# Bank33.net
KiCad netlist of a schematic drawn in Altium Designer
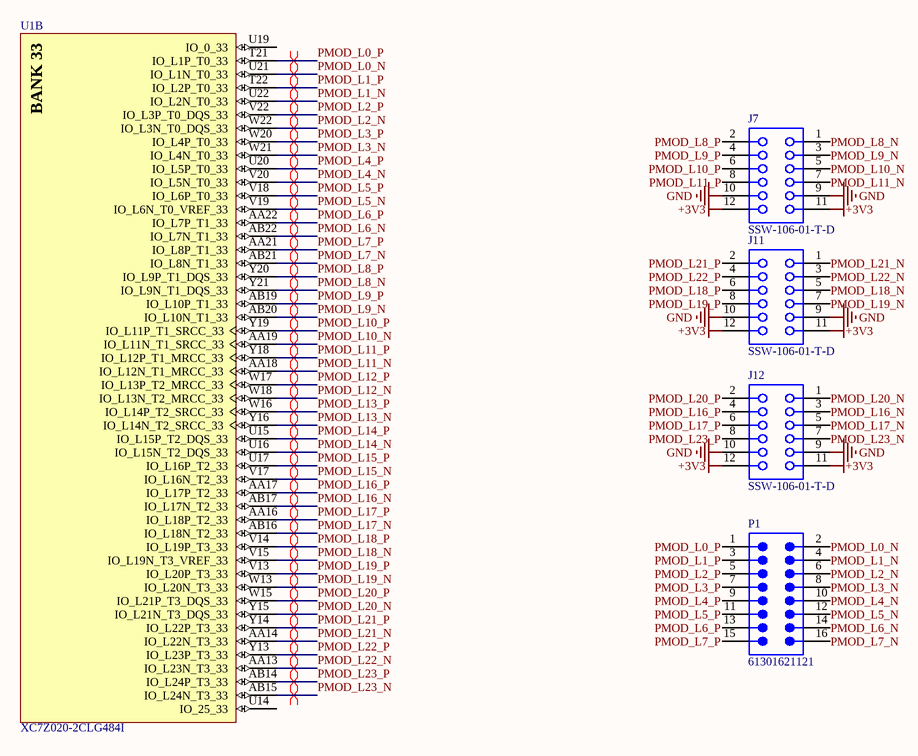
[diagram p0: Bank33.SchDoc]

(export (version "E")
  (design (tool "Eeschema 10.0.6"))
  (components
    (comp (ref "J7")
      (value "SSW-106-01-T-D")
      (footprint "SMTC-SSW-106-01-X-D")
      (description "SQ Post Socket, Through-hole, Vertical, -55 to 105 degC, 2.54mm Pitch, 12-Pin, Female, RoHS")
      (fields (field (name "MANUFACTURER") "Samtec"))
      (libsource (lib "Altium Content Vault") (part "SMTC-SSW-106-01-X-D"))
    )
    (comp (ref "J11")
      (value "SSW-106-01-T-D")
      (footprint "SMTC-SSW-106-01-X-D")
      (description "SQ Post Socket, Through-hole, Vertical, -55 to 105 degC, 2.54mm Pitch, 12-Pin, Female, RoHS")
      (fields (field (name "MANUFACTURER") "Samtec"))
      (libsource (lib "Altium Content Vault") (part "SMTC-SSW-106-01-X-D"))
    )
    (comp (ref "J12")
      (value "SSW-106-01-T-D")
      (footprint "SMTC-SSW-106-01-X-D")
      (description "SQ Post Socket, Through-hole, Vertical, -55 to 105 degC, 2.54mm Pitch, 12-Pin, Female, RoHS")
      (fields (field (name "MANUFACTURER") "Samtec"))
      (libsource (lib "Altium Content Vault") (part "SMTC-SSW-106-01-X-D"))
    )
    (comp (ref "P1")
      (value "61301621121")
      (footprint "61301621121")
      (libsource (lib "Altium Content Vault") (part "Header_Male_2R_16P"))
    )
    (comp (ref "U1")
      (value "XC7Z020-2CLG484I")
      (footprint "CLG484")
      (fields (field (name "GENERIC PART NUMBER") "XC7Z020"))
      (libsource (lib "Altium Content Vault") (part "XNLX-XC7Z020-CLG484"))
    )
  )
  (nets
    (net (code "1") (name "+3V3") (class "Default")
      (node (ref "J11") (pin "11") (pinfunction "11_11") (pintype "passive"))
      (node (ref "J11") (pin "12") (pinfunction "12_12") (pintype "passive"))
      (node (ref "J12") (pin "11") (pinfunction "11_11") (pintype "passive"))
      (node (ref "J12") (pin "12") (pinfunction "12_12") (pintype "passive"))
      (node (ref "J7") (pin "11") (pinfunction "11_11") (pintype "passive"))
      (node (ref "J7") (pin "12") (pinfunction "12_12") (pintype "passive"))
    )
    (net (code "2") (name "/PMOD_L0_N") (class "Default")
      (node (ref "P1") (pin "2") (pinfunction "2_2") (pintype "passive"))
      (node (ref "U1") (pin "U21") (pinfunction "IO_L1N_T0_33_U21") (pintype "bidirectional"))
    )
    (net (code "3") (name "/PMOD_L0_P") (class "Default")
      (node (ref "P1") (pin "1") (pinfunction "1_1") (pintype "passive"))
      (node (ref "U1") (pin "T21") (pinfunction "IO_L1P_T0_33_T21") (pintype "bidirectional"))
    )
    (net (code "4") (name "/PMOD_L1_N") (class "Default")
      (node (ref "P1") (pin "4") (pinfunction "4_4") (pintype "passive"))
      (node (ref "U1") (pin "U22") (pinfunction "IO_L2N_T0_33_U22") (pintype "bidirectional"))
    )
    (net (code "5") (name "/PMOD_L1_P") (class "Default")
      (node (ref "P1") (pin "3") (pinfunction "3_3") (pintype "passive"))
      (node (ref "U1") (pin "T22") (pinfunction "IO_L2P_T0_33_T22") (pintype "bidirectional"))
    )
    (net (code "6") (name "/PMOD_L2_N") (class "Default")
      (node (ref "P1") (pin "6") (pinfunction "6_6") (pintype "passive"))
      (node (ref "U1") (pin "W22") (pinfunction "IO_L3N_T0_DQS_33_W22") (pintype "bidirectional"))
    )
    (net (code "7") (name "/PMOD_L2_P") (class "Default")
      (node (ref "P1") (pin "5") (pinfunction "5_5") (pintype "passive"))
      (node (ref "U1") (pin "V22") (pinfunction "IO_L3P_T0_DQS_33_V22") (pintype "bidirectional"))
    )
    (net (code "8") (name "/PMOD_L3_N") (class "Default")
      (node (ref "P1") (pin "8") (pinfunction "8_8") (pintype "passive"))
      (node (ref "U1") (pin "W21") (pinfunction "IO_L4N_T0_33_W21") (pintype "bidirectional"))
    )
    (net (code "9") (name "/PMOD_L3_P") (class "Default")
      (node (ref "P1") (pin "7") (pinfunction "7_7") (pintype "passive"))
      (node (ref "U1") (pin "W20") (pinfunction "IO_L4P_T0_33_W20") (pintype "bidirectional"))
    )
    (net (code "10") (name "/PMOD_L4_N") (class "Default")
      (node (ref "P1") (pin "10") (pinfunction "10_10") (pintype "passive"))
      (node (ref "U1") (pin "V20") (pinfunction "IO_L5N_T0_33_V20") (pintype "bidirectional"))
    )
    (net (code "11") (name "/PMOD_L4_P") (class "Default")
      (node (ref "P1") (pin "9") (pinfunction "9_9") (pintype "passive"))
      (node (ref "U1") (pin "U20") (pinfunction "IO_L5P_T0_33_U20") (pintype "bidirectional"))
    )
    (net (code "12") (name "/PMOD_L5_N") (class "Default")
      (node (ref "P1") (pin "12") (pinfunction "12_12") (pintype "passive"))
      (node (ref "U1") (pin "V19") (pinfunction "IO_L6N_T0_VREF_33_V19") (pintype "bidirectional"))
    )
    (net (code "13") (name "/PMOD_L5_P") (class "Default")
      (node (ref "P1") (pin "11") (pinfunction "11_11") (pintype "passive"))
      (node (ref "U1") (pin "V18") (pinfunction "IO_L6P_T0_33_V18") (pintype "bidirectional"))
    )
    (net (code "14") (name "/PMOD_L6_N") (class "Default")
      (node (ref "P1") (pin "14") (pinfunction "14_14") (pintype "passive"))
      (node (ref "U1") (pin "AB22") (pinfunction "IO_L7N_T1_33_AB22") (pintype "bidirectional"))
    )
    (net (code "15") (name "/PMOD_L6_P") (class "Default")
      (node (ref "P1") (pin "13") (pinfunction "13_13") (pintype "passive"))
      (node (ref "U1") (pin "AA22") (pinfunction "IO_L7P_T1_33_AA22") (pintype "bidirectional"))
    )
    (net (code "16") (name "/PMOD_L7_N") (class "Default")
      (node (ref "P1") (pin "16") (pinfunction "16_16") (pintype "passive"))
      (node (ref "U1") (pin "AB21") (pinfunction "IO_L8N_T1_33_AB21") (pintype "bidirectional"))
    )
    (net (code "17") (name "/PMOD_L7_P") (class "Default")
      (node (ref "P1") (pin "15") (pinfunction "15_15") (pintype "passive"))
      (node (ref "U1") (pin "AA21") (pinfunction "IO_L8P_T1_33_AA21") (pintype "bidirectional"))
    )
    (net (code "18") (name "/PMOD_L8_N") (class "Default")
      (node (ref "J7") (pin "1") (pinfunction "1_1") (pintype "passive"))
      (node (ref "U1") (pin "Y21") (pinfunction "IO_L9N_T1_DQS_33_Y21") (pintype "bidirectional"))
    )
    (net (code "19") (name "/PMOD_L8_P") (class "Default")
      (node (ref "J7") (pin "2") (pinfunction "2_2") (pintype "passive"))
      (node (ref "U1") (pin "Y20") (pinfunction "IO_L9P_T1_DQS_33_Y20") (pintype "bidirectional"))
    )
    (net (code "20") (name "/PMOD_L9_N") (class "Default")
      (node (ref "J7") (pin "3") (pinfunction "3_3") (pintype "passive"))
      (node (ref "U1") (pin "AB20") (pinfunction "IO_L10N_T1_33_AB20") (pintype "bidirectional"))
    )
    (net (code "21") (name "/PMOD_L9_P") (class "Default")
      (node (ref "J7") (pin "4") (pinfunction "4_4") (pintype "passive"))
      (node (ref "U1") (pin "AB19") (pinfunction "IO_L10P_T1_33_AB19") (pintype "bidirectional"))
    )
    (net (code "22") (name "/PMOD_L10_N") (class "Default")
      (node (ref "J7") (pin "5") (pinfunction "5_5") (pintype "passive"))
      (node (ref "U1") (pin "AA19") (pinfunction "IO_L11N_T1_SRCC_33_AA19") (pintype "bidirectional"))
    )
    (net (code "23") (name "/PMOD_L10_P") (class "Default")
      (node (ref "J7") (pin "6") (pinfunction "6_6") (pintype "passive"))
      (node (ref "U1") (pin "Y19") (pinfunction "IO_L11P_T1_SRCC_33_Y19") (pintype "bidirectional"))
    )
    (net (code "24") (name "/PMOD_L11_N") (class "Default")
      (node (ref "J7") (pin "7") (pinfunction "7_7") (pintype "passive"))
      (node (ref "U1") (pin "AA18") (pinfunction "IO_L12N_T1_MRCC_33_AA18") (pintype "bidirectional"))
    )
    (net (code "25") (name "/PMOD_L11_P") (class "Default")
      (node (ref "J7") (pin "8") (pinfunction "8_8") (pintype "passive"))
      (node (ref "U1") (pin "Y18") (pinfunction "IO_L12P_T1_MRCC_33_Y18") (pintype "bidirectional"))
    )
    (net (code "26") (name "/PMOD_L12_N") (class "Default")
      (node (ref "U1") (pin "W18") (pinfunction "IO_L13N_T2_MRCC_33_W18") (pintype "bidirectional"))
    )
    (net (code "27") (name "/PMOD_L12_P") (class "Default")
      (node (ref "U1") (pin "W17") (pinfunction "IO_L13P_T2_MRCC_33_W17") (pintype "bidirectional"))
    )
    (net (code "28") (name "/PMOD_L13_N") (class "Default")
      (node (ref "U1") (pin "Y16") (pinfunction "IO_L14N_T2_SRCC_33_Y16") (pintype "bidirectional"))
    )
    (net (code "29") (name "/PMOD_L13_P") (class "Default")
      (node (ref "U1") (pin "W16") (pinfunction "IO_L14P_T2_SRCC_33_W16") (pintype "bidirectional"))
    )
    (net (code "30") (name "/PMOD_L14_N") (class "Default")
      (node (ref "U1") (pin "U16") (pinfunction "IO_L15N_T2_DQS_33_U16") (pintype "bidirectional"))
    )
    (net (code "31") (name "/PMOD_L14_P") (class "Default")
      (node (ref "U1") (pin "U15") (pinfunction "IO_L15P_T2_DQS_33_U15") (pintype "bidirectional"))
    )
    (net (code "32") (name "/PMOD_L15_N") (class "Default")
      (node (ref "U1") (pin "V17") (pinfunction "IO_L16N_T2_33_V17") (pintype "bidirectional"))
    )
    (net (code "33") (name "/PMOD_L15_P") (class "Default")
      (node (ref "U1") (pin "U17") (pinfunction "IO_L16P_T2_33_U17") (pintype "bidirectional"))
    )
    (net (code "34") (name "/PMOD_L16_N") (class "Default")
      (node (ref "J12") (pin "3") (pinfunction "3_3") (pintype "passive"))
      (node (ref "U1") (pin "AB17") (pinfunction "IO_L17N_T2_33_AB17") (pintype "bidirectional"))
    )
    (net (code "35") (name "/PMOD_L16_P") (class "Default")
      (node (ref "J12") (pin "4") (pinfunction "4_4") (pintype "passive"))
      (node (ref "U1") (pin "AA17") (pinfunction "IO_L17P_T2_33_AA17") (pintype "bidirectional"))
    )
    (net (code "36") (name "/PMOD_L17_N") (class "Default")
      (node (ref "J12") (pin "5") (pinfunction "5_5") (pintype "passive"))
      (node (ref "U1") (pin "AB16") (pinfunction "IO_L18N_T2_33_AB16") (pintype "bidirectional"))
    )
    (net (code "37") (name "/PMOD_L17_P") (class "Default")
      (node (ref "J12") (pin "6") (pinfunction "6_6") (pintype "passive"))
      (node (ref "U1") (pin "AA16") (pinfunction "IO_L18P_T2_33_AA16") (pintype "bidirectional"))
    )
    (net (code "38") (name "/PMOD_L18_N") (class "Default")
      (node (ref "J11") (pin "5") (pinfunction "5_5") (pintype "passive"))
      (node (ref "U1") (pin "V15") (pinfunction "IO_L19N_T3_VREF_33_V15") (pintype "bidirectional"))
    )
    (net (code "39") (name "/PMOD_L18_P") (class "Default")
      (node (ref "J11") (pin "6") (pinfunction "6_6") (pintype "passive"))
      (node (ref "U1") (pin "V14") (pinfunction "IO_L19P_T3_33_V14") (pintype "bidirectional"))
    )
    (net (code "40") (name "/PMOD_L19_N") (class "Default")
      (node (ref "J11") (pin "7") (pinfunction "7_7") (pintype "passive"))
      (node (ref "U1") (pin "W13") (pinfunction "IO_L20N_T3_33_W13") (pintype "bidirectional"))
    )
    (net (code "41") (name "/PMOD_L19_P") (class "Default")
      (node (ref "J11") (pin "8") (pinfunction "8_8") (pintype "passive"))
      (node (ref "U1") (pin "V13") (pinfunction "IO_L20P_T3_33_V13") (pintype "bidirectional"))
    )
    (net (code "42") (name "/PMOD_L20_N") (class "Default")
      (node (ref "J12") (pin "1") (pinfunction "1_1") (pintype "passive"))
      (node (ref "U1") (pin "Y15") (pinfunction "IO_L21N_T3_DQS_33_Y15") (pintype "bidirectional"))
    )
    (net (code "43") (name "/PMOD_L20_P") (class "Default")
      (node (ref "J12") (pin "2") (pinfunction "2_2") (pintype "passive"))
      (node (ref "U1") (pin "W15") (pinfunction "IO_L21P_T3_DQS_33_W15") (pintype "bidirectional"))
    )
    (net (code "44") (name "/PMOD_L21_N") (class "Default")
      (node (ref "J11") (pin "1") (pinfunction "1_1") (pintype "passive"))
      (node (ref "U1") (pin "AA14") (pinfunction "IO_L22N_T3_33_AA14") (pintype "bidirectional"))
    )
    (net (code "45") (name "/PMOD_L21_P") (class "Default")
      (node (ref "J11") (pin "2") (pinfunction "2_2") (pintype "passive"))
      (node (ref "U1") (pin "Y14") (pinfunction "IO_L22P_T3_33_Y14") (pintype "bidirectional"))
    )
    (net (code "46") (name "/PMOD_L22_N") (class "Default")
      (node (ref "J11") (pin "3") (pinfunction "3_3") (pintype "passive"))
      (node (ref "U1") (pin "AA13") (pinfunction "IO_L23N_T3_33_AA13") (pintype "bidirectional"))
    )
    (net (code "47") (name "/PMOD_L22_P") (class "Default")
      (node (ref "J11") (pin "4") (pinfunction "4_4") (pintype "passive"))
      (node (ref "U1") (pin "Y13") (pinfunction "IO_L23P_T3_33_Y13") (pintype "bidirectional"))
    )
    (net (code "48") (name "/PMOD_L23_N") (class "Default")
      (node (ref "J12") (pin "7") (pinfunction "7_7") (pintype "passive"))
      (node (ref "U1") (pin "AB15") (pinfunction "IO_L24N_T3_33_AB15") (pintype "bidirectional"))
    )
    (net (code "49") (name "/PMOD_L23_P") (class "Default")
      (node (ref "J12") (pin "8") (pinfunction "8_8") (pintype "passive"))
      (node (ref "U1") (pin "AB14") (pinfunction "IO_L24P_T3_33_AB14") (pintype "bidirectional"))
    )
    (net (code "50") (name "GND") (class "Default")
      (node (ref "J11") (pin "10") (pinfunction "10_10") (pintype "passive"))
      (node (ref "J11") (pin "9") (pinfunction "9_9") (pintype "passive"))
      (node (ref "J12") (pin "10") (pinfunction "10_10") (pintype "passive"))
      (node (ref "J12") (pin "9") (pinfunction "9_9") (pintype "passive"))
      (node (ref "J7") (pin "10") (pinfunction "10_10") (pintype "passive"))
      (node (ref "J7") (pin "9") (pinfunction "9_9") (pintype "passive"))
    )
    (net (code "51") (name "unconnected-(U1B-IO_0_33-PadU19)") (class "Default")
      (node (ref "U1") (pin "U19") (pinfunction "IO_0_33_U19") (pintype "bidirectional"))
    )
    (net (code "52") (name "unconnected-(U1B-IO_25_33-PadU14)") (class "Default")
      (node (ref "U1") (pin "U14") (pinfunction "IO_25_33_U14") (pintype "bidirectional"))
    )
  )
)
